# Atomizer.net
KiCad netlist of a schematic drawn in Altium Designer
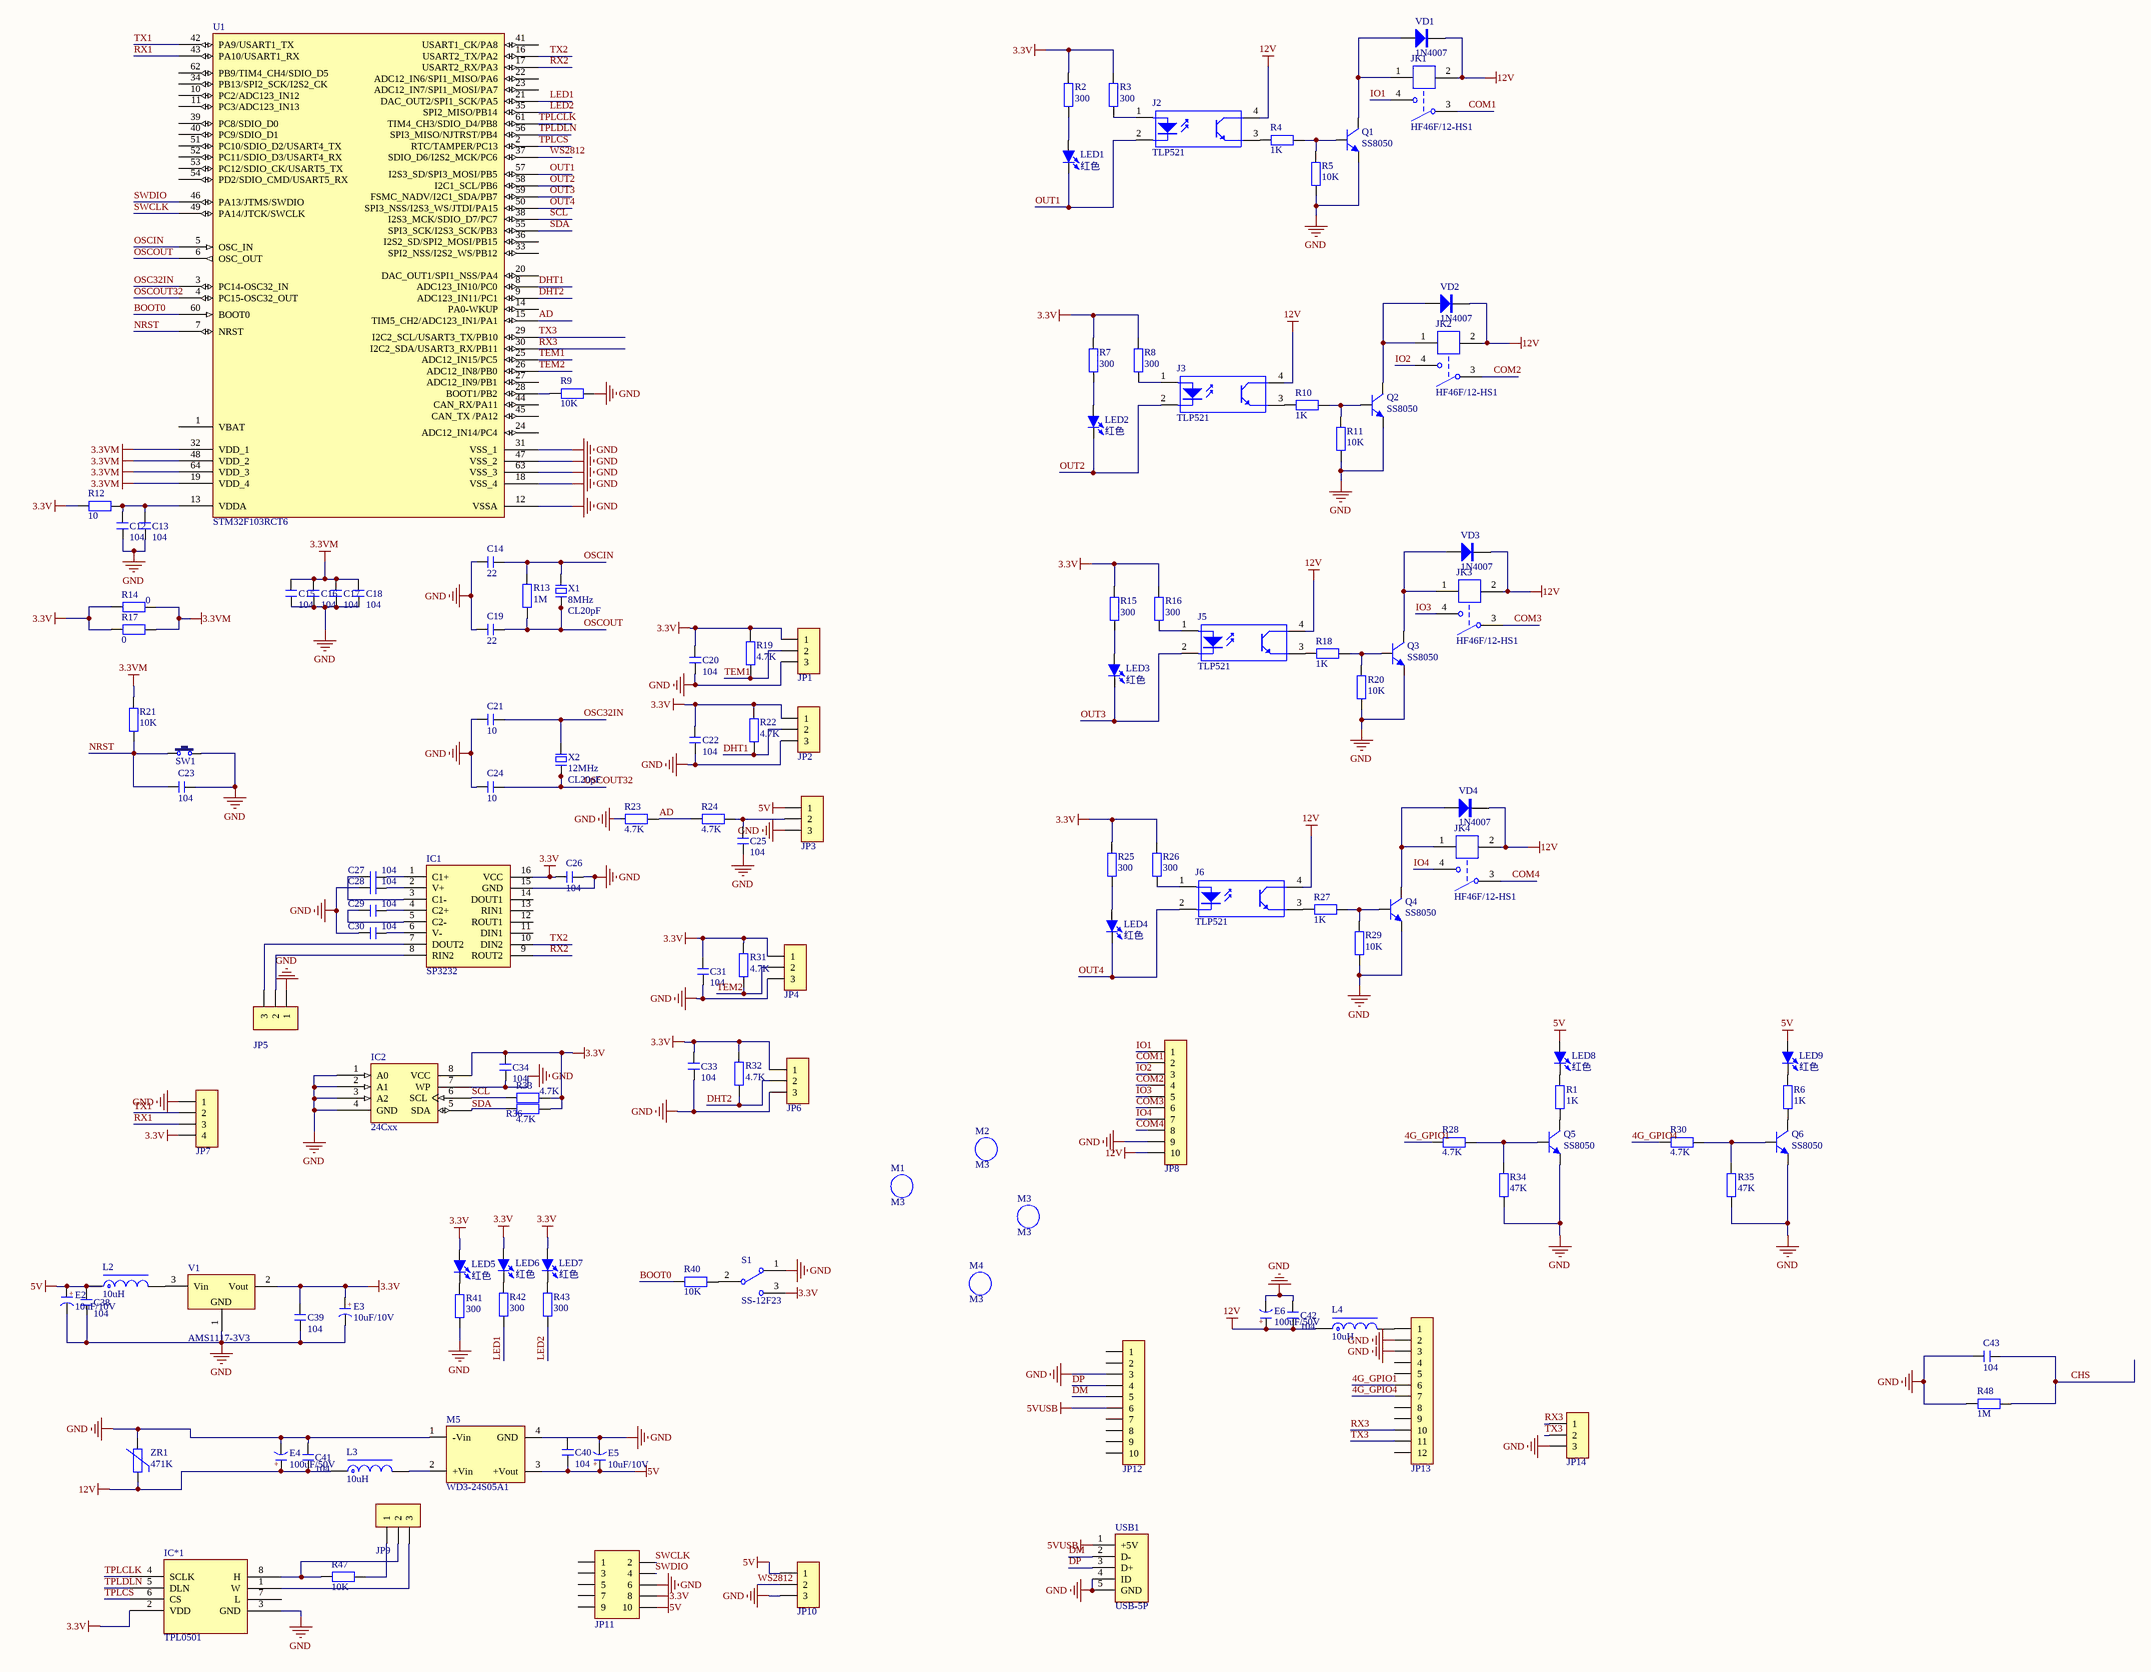
[diagram p0: Atomizer.SchDoc]

(export (version "E")
  (design (tool "Eeschema 10.0.6"))
  (components
    (comp (ref "C12")
      (value "104")
      (footprint "C 0805_M")
      (description "无极性贴片电容")
      (fields (field (name "版权归属") "源创客"))
      (libsource (lib "电阻-电容-电感") (part "C"))
    )
    (comp (ref "C13")
      (value "104")
      (footprint "C 0805_M")
      (description "无极性贴片电容")
      (fields (field (name "版权归属") "源创客"))
      (libsource (lib "电阻-电容-电感") (part "C"))
    )
    (comp (ref "C14")
      (value "22")
      (footprint "C 0805_M")
      (description "无极性贴片电容")
      (fields (field (name "版权归属") "源创客"))
      (libsource (lib "电阻-电容-电感") (part "C"))
    )
    (comp (ref "C15")
      (value "104")
      (footprint "C 0805_M")
      (description "无极性贴片电容")
      (fields (field (name "版权归属") "源创客"))
      (libsource (lib "电阻-电容-电感") (part "C"))
    )
    (comp (ref "C16")
      (value "104")
      (footprint "C 0805_M")
      (description "无极性贴片电容")
      (fields (field (name "版权归属") "源创客"))
      (libsource (lib "电阻-电容-电感") (part "C"))
    )
    (comp (ref "C17")
      (value "104")
      (footprint "C 0805_M")
      (description "无极性贴片电容")
      (fields (field (name "版权归属") "源创客"))
      (libsource (lib "电阻-电容-电感") (part "C"))
    )
    (comp (ref "C18")
      (value "104")
      (footprint "C 0805_M")
      (description "无极性贴片电容")
      (fields (field (name "版权归属") "源创客"))
      (libsource (lib "电阻-电容-电感") (part "C"))
    )
    (comp (ref "C19")
      (value "22")
      (footprint "C 0805_M")
      (description "无极性贴片电容")
      (fields (field (name "版权归属") "源创客"))
      (libsource (lib "电阻-电容-电感") (part "C"))
    )
    (comp (ref "C20")
      (value "104")
      (footprint "C 0805_M")
      (description "无极性贴片电容")
      (fields (field (name "版权归属") "源创客"))
      (libsource (lib "电阻-电容-电感") (part "C"))
    )
    (comp (ref "C21")
      (value "10")
      (footprint "C 0805_M")
      (description "无极性贴片电容")
      (fields (field (name "版权归属") "源创客"))
      (libsource (lib "电阻-电容-电感") (part "C"))
    )
    (comp (ref "C22")
      (value "104")
      (footprint "C 0805_M")
      (description "无极性贴片电容")
      (fields (field (name "版权归属") "源创客"))
      (libsource (lib "电阻-电容-电感") (part "C"))
    )
    (comp (ref "C23")
      (value "104")
      (footprint "C 0805_M")
      (description "无极性贴片电容")
      (fields (field (name "版权归属") "源创客"))
      (libsource (lib "电阻-电容-电感") (part "C"))
    )
    (comp (ref "C24")
      (value "10")
      (footprint "C 0805_M")
      (description "无极性贴片电容")
      (fields (field (name "版权归属") "源创客"))
      (libsource (lib "电阻-电容-电感") (part "C"))
    )
    (comp (ref "C25")
      (value "104")
      (footprint "C 0805_M")
      (description "无极性贴片电容")
      (fields (field (name "版权归属") "源创客"))
      (libsource (lib "电阻-电容-电感") (part "C"))
    )
    (comp (ref "C26")
      (value "104")
      (footprint "C 0805_M")
      (description "无极性贴片电容")
      (fields (field (name "版权归属") "源创客"))
      (libsource (lib "电阻-电容-电感") (part "C"))
    )
    (comp (ref "C27")
      (value "104")
      (footprint "C 0805_M")
      (description "无极性贴片电容")
      (fields (field (name "版权归属") "源创客"))
      (libsource (lib "电阻-电容-电感") (part "C"))
    )
    (comp (ref "C28")
      (value "104")
      (footprint "C 0805_M")
      (description "无极性贴片电容")
      (fields (field (name "版权归属") "源创客"))
      (libsource (lib "电阻-电容-电感") (part "C"))
    )
    (comp (ref "C29")
      (value "104")
      (footprint "C 0805_M")
      (description "无极性贴片电容")
      (fields (field (name "版权归属") "源创客"))
      (libsource (lib "电阻-电容-电感") (part "C"))
    )
    (comp (ref "C30")
      (value "104")
      (footprint "C 0805_M")
      (description "无极性贴片电容")
      (fields (field (name "版权归属") "源创客"))
      (libsource (lib "电阻-电容-电感") (part "C"))
    )
    (comp (ref "C31")
      (value "104")
      (footprint "C 0805_M")
      (description "无极性贴片电容")
      (fields (field (name "版权归属") "源创客"))
      (libsource (lib "电阻-电容-电感") (part "C"))
    )
    (comp (ref "C33")
      (value "104")
      (footprint "C 0805_M")
      (description "无极性贴片电容")
      (fields (field (name "版权归属") "源创客"))
      (libsource (lib "电阻-电容-电感") (part "C"))
    )
    (comp (ref "C34")
      (value "104")
      (footprint "C 0805_M")
      (description "无极性贴片电容")
      (fields (field (name "版权归属") "源创客"))
      (libsource (lib "电阻-电容-电感") (part "C"))
    )
    (comp (ref "C38")
      (value "104")
      (footprint "C 0805_M")
      (description "无极性贴片电容")
      (fields (field (name "版权归属") "源创客"))
      (libsource (lib "电阻-电容-电感") (part "C"))
    )
    (comp (ref "C39")
      (value "104")
      (footprint "C 0805_M")
      (description "无极性贴片电容")
      (fields (field (name "版权归属") "源创客"))
      (libsource (lib "电阻-电容-电感") (part "C"))
    )
    (comp (ref "C40")
      (value "104")
      (footprint "C 0805_M")
      (description "无极性贴片电容")
      (fields (field (name "版权归属") "源创客"))
      (libsource (lib "电阻-电容-电感") (part "C"))
    )
    (comp (ref "C41")
      (value "104")
      (footprint "C 0805_M")
      (description "无极性贴片电容")
      (fields (field (name "版权归属") "源创客"))
      (libsource (lib "电阻-电容-电感") (part "C"))
    )
    (comp (ref "C42")
      (value "104")
      (footprint "C 0805_M")
      (description "无极性贴片电容")
      (fields (field (name "版权归属") "源创客"))
      (libsource (lib "电阻-电容-电感") (part "C"))
    )
    (comp (ref "C43")
      (value "104")
      (footprint "C 1206_L")
      (description "无极性贴片电容")
      (fields (field (name "版权归属") "源创客"))
      (libsource (lib "3.1   - 电阻-电容-电感") (part "C"))
    )
    (comp (ref "E2")
      (value "10uF/10V")
      (footprint "CT 5*6 - C")
      (description "贴片固态电容")
      (fields (field (name "版权归属") "源创客"))
      (libsource (lib "3.1   - 电阻-电容-电感") (part "C-CT"))
    )
    (comp (ref "E3")
      (value "10uF/10V")
      (footprint "CM C(5*5.4)")
      (description "贴片电解电容")
      (fields (field (name "版权归属") "源创客"))
      (libsource (lib "电阻-电容-电感") (part "C-CM"))
    )
    (comp (ref "E4")
      (value "100uF/50V")
      (footprint "CT 10*8 - C")
      (description "贴片固态电容")
      (fields (field (name "版权归属") "源创客"))
      (libsource (lib "3.1   - 电阻-电容-电感") (part "C-CT"))
    )
    (comp (ref "E5")
      (value "10uF/10V")
      (footprint "CT 5*6 - C")
      (description "贴片固态电容")
      (fields (field (name "版权归属") "源创客"))
      (libsource (lib "3.1   - 电阻-电容-电感") (part "C-CT"))
    )
    (comp (ref "E6")
      (value "100uF/50V")
      (footprint "CT 10*8 - C")
      (description "贴片固态电容")
      (fields (field (name "版权归属") "源创客"))
      (libsource (lib "3.1   - 电阻-电容-电感") (part "C-CT"))
    )
    (comp (ref "IC*1")
      (value "TPL0501")
      (footprint "SOT23-8L")
      (description "数字电位器")
      (libsource (lib "IC芯片") (part "TPL0501"))
    )
    (comp (ref "IC1")
      (value "SP3232")
      (footprint "TSSOP-16")
      (description "RS232通讯芯片")
      (fields (field (name "版权归属") "源创客"))
      (libsource (lib "IC芯片") (part "SP3232"))
    )
    (comp (ref "IC2")
      (value "24Cxx")
      (footprint "SOP8_L")
      (description "外置EEPROM")
      (fields (field (name "版权归属") "源创客"))
      (libsource (lib "IC芯片") (part "24Cxx"))
    )
    (comp (ref "J2")
      (value "TLP521")
      (footprint "DIP4-300")
      (description "开关光耦")
      (fields (field (name "版权归属") "源创客"))
      (libsource (lib "传感元件") (part "TLP521"))
    )
    (comp (ref "J3")
      (value "TLP521")
      (footprint "DIP4-300")
      (description "开关光耦")
      (fields (field (name "版权归属") "源创客"))
      (libsource (lib "传感元件") (part "TLP521"))
    )
    (comp (ref "J5")
      (value "TLP521")
      (footprint "DIP4-300")
      (description "开关光耦")
      (fields (field (name "版权归属") "源创客"))
      (libsource (lib "传感元件") (part "TLP521"))
    )
    (comp (ref "J6")
      (value "TLP521")
      (footprint "DIP4-300")
      (description "开关光耦")
      (fields (field (name "版权归属") "源创客"))
      (libsource (lib "传感元件") (part "TLP521"))
    )
    (comp (ref "JK1")
      (value "HF46F/12-HS1")
      (footprint "HF46-xx-HS1")
      (description "12V一组常开")
      (fields (field (name "版权归属") "源创客"))
      (libsource (lib "7.1   - 继电器") (part "HF46F/12-HS1"))
    )
    (comp (ref "JK2")
      (value "HF46F/12-HS1")
      (footprint "HF46-xx-HS1")
      (description "12V一组常开")
      (fields (field (name "版权归属") "源创客"))
      (libsource (lib "7.1   - 继电器") (part "HF46F/12-HS1"))
    )
    (comp (ref "JK3")
      (value "HF46F/12-HS1")
      (footprint "HF46-xx-HS1")
      (description "12V一组常开")
      (fields (field (name "版权归属") "源创客"))
      (libsource (lib "7.1   - 继电器") (part "HF46F/12-HS1"))
    )
    (comp (ref "JK4")
      (value "HF46F/12-HS1")
      (footprint "HF46-xx-HS1")
      (description "12V一组常开")
      (fields (field (name "版权归属") "源创客"))
      (libsource (lib "7.1   - 继电器") (part "HF46F/12-HS1"))
    )
    (comp (ref "JP1")
      (value "HDR-1X3")
      (footprint "KF128-3.81-3P")
      (description "3P接插件")
      (fields (field (name "版权归属") "源创客"))
      (libsource (lib "接插件") (part "Header 3"))
    )
    (comp (ref "JP2")
      (value "HDR-1X3")
      (footprint "KF128-3.81-3P")
      (description "3P接插件")
      (fields (field (name "版权归属") "源创客"))
      (libsource (lib "接插件") (part "Header 3"))
    )
    (comp (ref "JP3")
      (value "HDR-1X3")
      (footprint "KF128-3.81-3P")
      (description "3P接插件")
      (fields (field (name "版权归属") "源创客"))
      (libsource (lib "接插件") (part "Header 3"))
    )
    (comp (ref "JP4")
      (value "HDR-1X3")
      (footprint "KF128-3.81-3P")
      (description "3P接插件")
      (fields (field (name "版权归属") "源创客"))
      (libsource (lib "接插件") (part "Header 3"))
    )
    (comp (ref "JP5")
      (value "HDR-1X3")
      (footprint "XH2.54-LI-3P")
      (description "3P接插件")
      (fields (field (name "版权归属") "源创客"))
      (libsource (lib "4.6   - 接插件-脚距2.54") (part "Header 3"))
    )
    (comp (ref "JP6")
      (value "HDR-1X3")
      (footprint "KF128-3.81-3P")
      (description "3P接插件")
      (fields (field (name "版权归属") "源创客"))
      (libsource (lib "接插件") (part "Header 3"))
    )
    (comp (ref "JP7")
      (value "HDR-1X4")
      (footprint "HDR2.54-LI-4P")
      (description "4P接插件")
      (fields (field (name "版权归属") "源创客"))
      (libsource (lib "4.6   - 接插件-脚距2.54") (part "Header 4"))
    )
    (comp (ref "JP8")
      (value "HDR-1X10")
      (footprint "KF128-5.08-10P")
      (description "10P接插件")
      (fields (field (name "版权归属") "源创客"))
      (libsource (lib "接插件") (part "Header 10"))
    )
    (comp (ref "JP9")
      (value "HDR-1X3")
      (footprint "KF128-3.81-3P")
      (description "3P接插件")
      (fields (field (name "版权归属") "源创客"))
      (libsource (lib "") (part "Header 3_1"))
    )
    (comp (ref "JP10")
      (value "HDR-1X3")
      (footprint "KF128-3.81-3P")
      (description "3P接插件")
      (fields (field (name "版权归属") "源创客"))
      (libsource (lib "接插件") (part "Header 3"))
    )
    (comp (ref "JP11")
      (value "Header 5X2")
      (footprint "IDC2.54-LI-2x5P")
      (description "5*2P接插件")
      (fields (field (name "版权归属") "源创客"))
      (libsource (lib "4.6   - 接插件-脚距2.54") (part "Header 5X2"))
    )
    (comp (ref "JP12")
      (value "HDR-1X10")
      (footprint "HDR2.54-M-LI-10P")
      (description "10P接插件")
      (fields (field (name "版权归属") "源创客"))
      (libsource (lib "4.6   - 接插件-脚距2.54") (part "Header 10"))
    )
    (comp (ref "JP13")
      (value "HDR-1X12")
      (footprint "HDR2.54-M-LI-12P")
      (description "12P接插件")
      (fields (field (name "版权归属") "源创客"))
      (libsource (lib "4.6   - 接插件-脚距2.54") (part "Header 12"))
    )
    (comp (ref "JP14")
      (value "HDR-1X3")
      (footprint "HDR2.54-LI-3P")
      (description "3P接插件")
      (fields (field (name "版权归属") "源创客"))
      (libsource (lib "") (part "Header 3_1"))
    )
    (comp (ref "L2")
      (value "10uH")
      (footprint "CD32")
      (description "贴片功率电感")
      (fields (field (name "版权归属") "源创客"))
      (libsource (lib "3.1   - 电阻-电容-电感") (part "L-CD"))
    )
    (comp (ref "L3")
      (value "10uH")
      (footprint "CD32")
      (description "贴片功率电感")
      (fields (field (name "版权归属") "源创客"))
      (libsource (lib "3.1   - 电阻-电容-电感") (part "L-CD"))
    )
    (comp (ref "L4")
      (value "10uH")
      (footprint "CD32")
      (description "贴片功率电感")
      (fields (field (name "版权归属") "源创客"))
      (libsource (lib "3.1   - 电阻-电容-电感") (part "L-CD"))
    )
    (comp (ref "LED1")
      (value "红色")
      (footprint "0805_LED_S1")
      (description "贴片LED")
      (fields (field (name "版权归属") "源创客"))
      (libsource (lib "LED") (part "LED-SMD"))
    )
    (comp (ref "LED2")
      (value "红色")
      (footprint "0805_LED_S1")
      (description "贴片LED")
      (fields (field (name "版权归属") "源创客"))
      (libsource (lib "LED") (part "LED-SMD"))
    )
    (comp (ref "LED3")
      (value "红色")
      (footprint "0805_LED_S1")
      (description "贴片LED")
      (fields (field (name "版权归属") "源创客"))
      (libsource (lib "LED") (part "LED-SMD"))
    )
    (comp (ref "LED4")
      (value "红色")
      (footprint "0805_LED_S1")
      (description "贴片LED")
      (fields (field (name "版权归属") "源创客"))
      (libsource (lib "LED") (part "LED-SMD"))
    )
    (comp (ref "LED5")
      (value "红色")
      (footprint "0805_LED_S1")
      (description "贴片LED")
      (fields (field (name "版权归属") "源创客"))
      (libsource (lib "LED") (part "LED-SMD"))
    )
    (comp (ref "LED6")
      (value "红色")
      (footprint "0805_LED_S1")
      (description "贴片LED")
      (fields (field (name "版权归属") "源创客"))
      (libsource (lib "LED") (part "LED-SMD"))
    )
    (comp (ref "LED7")
      (value "红色")
      (footprint "0805_LED_S1")
      (description "贴片LED")
      (fields (field (name "版权归属") "源创客"))
      (libsource (lib "LED") (part "LED-SMD"))
    )
    (comp (ref "LED8")
      (value "红色")
      (footprint "0805_LED_S1")
      (description "贴片LED")
      (fields (field (name "版权归属") "源创客"))
      (libsource (lib "LED") (part "LED-SMD"))
    )
    (comp (ref "LED9")
      (value "红色")
      (footprint "0805_LED_S1")
      (description "贴片LED")
      (fields (field (name "版权归属") "源创客"))
      (libsource (lib "LED") (part "LED-SMD"))
    )
    (comp (ref "M1")
      (value "M3")
      (footprint "M3 125X200")
      (description "铜柱孔")
      (fields (field (name "版权归属") "源创客"))
      (libsource (lib "未分类器件") (part "M3"))
    )
    (comp (ref "M2")
      (value "M3")
      (footprint "M3 125X200")
      (description "铜柱孔")
      (fields (field (name "版权归属") "源创客"))
      (libsource (lib "未分类器件") (part "M3"))
    )
    (comp (ref "M3")
      (value "M3")
      (footprint "M3 125X200")
      (description "铜柱孔")
      (fields (field (name "版权归属") "源创客"))
      (libsource (lib "未分类器件") (part "M3"))
    )
    (comp (ref "M4")
      (value "M3")
      (footprint "M3 125X200")
      (description "铜柱孔")
      (fields (field (name "版权归属") "源创客"))
      (libsource (lib "未分类器件") (part "M3"))
    )
    (comp (ref "M5")
      (value "WD3-24S05A1")
      (footprint "WD-24S05A1")
      (description "24V转5V模块")
      (fields (field (name "版权归属") "源创客"))
      (libsource (lib "13.1 - 模块") (part "WD3-24S05A1"))
    )
    (comp (ref "Q1")
      (value "SS8050")
      (footprint "SOT23-3N")
      (description "高频放大-NPN型")
      (fields (field (name "版权归属") "源创客"))
      (libsource (lib "三极管") (part "8050-SMD"))
    )
    (comp (ref "Q2")
      (value "SS8050")
      (footprint "SOT23-3N")
      (description "高频放大-NPN型")
      (fields (field (name "版权归属") "源创客"))
      (libsource (lib "三极管") (part "8050-SMD"))
    )
    (comp (ref "Q3")
      (value "SS8050")
      (footprint "SOT23-3N")
      (description "高频放大-NPN型")
      (fields (field (name "版权归属") "源创客"))
      (libsource (lib "三极管") (part "8050-SMD"))
    )
    (comp (ref "Q4")
      (value "SS8050")
      (footprint "SOT23-3N")
      (description "高频放大-NPN型")
      (fields (field (name "版权归属") "源创客"))
      (libsource (lib "三极管") (part "8050-SMD"))
    )
    (comp (ref "Q5")
      (value "SS8050")
      (footprint "SOT23-3N")
      (description "高频放大-NPN型")
      (fields (field (name "版权归属") "源创客"))
      (libsource (lib "6.2   - 三极管") (part "8050-SMD"))
    )
    (comp (ref "Q6")
      (value "SS8050")
      (footprint "SOT23-3N")
      (description "高频放大-NPN型")
      (fields (field (name "版权归属") "源创客"))
      (libsource (lib "6.2   - 三极管") (part "8050-SMD"))
    )
    (comp (ref "R1")
      (value "1K")
      (footprint "R 0805_M")
      (description "贴片电阻")
      (fields (field (name "版权归属") "源创客"))
      (libsource (lib "电阻-电容-电感") (part "R"))
    )
    (comp (ref "R2")
      (value "300")
      (footprint "R 0805_M")
      (description "贴片电阻")
      (fields (field (name "版权归属") "源创客"))
      (libsource (lib "电阻-电容-电感") (part "R"))
    )
    (comp (ref "R3")
      (value "300")
      (footprint "R 0805_M")
      (description "贴片电阻")
      (fields (field (name "版权归属") "源创客"))
      (libsource (lib "电阻-电容-电感") (part "R"))
    )
    (comp (ref "R4")
      (value "1K")
      (footprint "R 0805_M")
      (description "贴片电阻")
      (fields (field (name "版权归属") "源创客"))
      (libsource (lib "电阻-电容-电感") (part "R"))
    )
    (comp (ref "R5")
      (value "10K")
      (footprint "R 0805_M")
      (description "贴片电阻")
      (fields (field (name "版权归属") "源创客"))
      (libsource (lib "电阻-电容-电感") (part "R"))
    )
    (comp (ref "R6")
      (value "1K")
      (footprint "R 0805_M")
      (description "贴片电阻")
      (fields (field (name "版权归属") "源创客"))
      (libsource (lib "电阻-电容-电感") (part "R"))
    )
    (comp (ref "R7")
      (value "300")
      (footprint "R 0805_M")
      (description "贴片电阻")
      (fields (field (name "版权归属") "源创客"))
      (libsource (lib "电阻-电容-电感") (part "R"))
    )
    (comp (ref "R8")
      (value "300")
      (footprint "R 0805_M")
      (description "贴片电阻")
      (fields (field (name "版权归属") "源创客"))
      (libsource (lib "电阻-电容-电感") (part "R"))
    )
    (comp (ref "R9")
      (value "10K")
      (footprint "R 0805_M")
      (description "贴片电阻")
      (fields (field (name "版权归属") "源创客"))
      (libsource (lib "电阻-电容-电感") (part "R"))
    )
    (comp (ref "R10")
      (value "1K")
      (footprint "R 0805_M")
      (description "贴片电阻")
      (fields (field (name "版权归属") "源创客"))
      (libsource (lib "电阻-电容-电感") (part "R"))
    )
    (comp (ref "R11")
      (value "10K")
      (footprint "R 0805_M")
      (description "贴片电阻")
      (fields (field (name "版权归属") "源创客"))
      (libsource (lib "电阻-电容-电感") (part "R"))
    )
    (comp (ref "R12")
      (value "10")
      (footprint "R 0805_M")
      (description "贴片电阻")
      (fields (field (name "版权归属") "源创客"))
      (libsource (lib "电阻-电容-电感") (part "R"))
    )
    (comp (ref "R13")
      (value "1M")
      (footprint "R 0805_M")
      (description "贴片电阻")
      (fields (field (name "版权归属") "源创客"))
      (libsource (lib "电阻-电容-电感") (part "R"))
    )
    (comp (ref "R14")
      (value "0")
      (footprint "R 0805_M")
      (description "贴片电阻")
      (fields (field (name "版权归属") "源创客"))
      (libsource (lib "电阻-电容-电感") (part "R"))
    )
    (comp (ref "R15")
      (value "300")
      (footprint "R 0805_M")
      (description "贴片电阻")
      (fields (field (name "版权归属") "源创客"))
      (libsource (lib "电阻-电容-电感") (part "R"))
    )
    (comp (ref "R16")
      (value "300")
      (footprint "R 0805_M")
      (description "贴片电阻")
      (fields (field (name "版权归属") "源创客"))
      (libsource (lib "电阻-电容-电感") (part "R"))
    )
    (comp (ref "R17")
      (value "0")
      (footprint "R 0805_M")
      (description "贴片电阻")
      (fields (field (name "版权归属") "源创客"))
      (libsource (lib "电阻-电容-电感") (part "R"))
    )
    (comp (ref "R18")
      (value "1K")
      (footprint "R 0805_M")
      (description "贴片电阻")
      (fields (field (name "版权归属") "源创客"))
      (libsource (lib "电阻-电容-电感") (part "R"))
    )
    (comp (ref "R19")
      (value "4.7K")
      (footprint "R 0805_M")
      (description "贴片电阻")
      (fields (field (name "版权归属") "源创客"))
      (libsource (lib "电阻-电容-电感") (part "R"))
    )
    (comp (ref "R20")
      (value "10K")
      (footprint "R 0805_M")
      (description "贴片电阻")
      (fields (field (name "版权归属") "源创客"))
      (libsource (lib "电阻-电容-电感") (part "R"))
    )
    (comp (ref "R21")
      (value "10K")
      (footprint "R 0805_M")
      (description "贴片电阻")
      (fields (field (name "版权归属") "源创客"))
      (libsource (lib "电阻-电容-电感") (part "R"))
    )
    (comp (ref "R22")
      (value "4.7K")
      (footprint "R 0805_M")
      (description "贴片电阻")
      (fields (field (name "版权归属") "源创客"))
      (libsource (lib "电阻-电容-电感") (part "R"))
    )
    (comp (ref "R23")
      (value "4.7K")
      (footprint "R 0805_M")
      (description "贴片电阻")
      (fields (field (name "版权归属") "源创客"))
      (libsource (lib "电阻-电容-电感") (part "R"))
    )
    (comp (ref "R24")
      (value "4.7K")
      (footprint "R 0805_M")
      (description "贴片电阻")
      (fields (field (name "版权归属") "源创客"))
      (libsource (lib "电阻-电容-电感") (part "R"))
    )
    (comp (ref "R25")
      (value "300")
      (footprint "R 0805_M")
      (description "贴片电阻")
      (fields (field (name "版权归属") "源创客"))
      (libsource (lib "电阻-电容-电感") (part "R"))
    )
    (comp (ref "R26")
      (value "300")
      (footprint "R 0805_M")
      (description "贴片电阻")
      (fields (field (name "版权归属") "源创客"))
      (libsource (lib "电阻-电容-电感") (part "R"))
    )
    (comp (ref "R27")
      (value "1K")
      (footprint "R 0805_M")
      (description "贴片电阻")
      (fields (field (name "版权归属") "源创客"))
      (libsource (lib "电阻-电容-电感") (part "R"))
    )
    (comp (ref "R28")
      (value "4.7K")
      (footprint "R 0805_M")
      (description "贴片电阻")
      (fields (field (name "版权归属") "源创客"))
      (libsource (lib "电阻-电容-电感") (part "R"))
    )
    (comp (ref "R29")
      (value "10K")
      (footprint "R 0805_M")
      (description "贴片电阻")
      (fields (field (name "版权归属") "源创客"))
      (libsource (lib "电阻-电容-电感") (part "R"))
    )
    (comp (ref "R30")
      (value "4.7K")
      (footprint "R 0805_M")
      (description "贴片电阻")
      (fields (field (name "版权归属") "源创客"))
      (libsource (lib "电阻-电容-电感") (part "R"))
    )
    (comp (ref "R31")
      (value "4.7K")
      (footprint "R 0805_M")
      (description "贴片电阻")
      (fields (field (name "版权归属") "源创客"))
      (libsource (lib "电阻-电容-电感") (part "R"))
    )
    (comp (ref "R32")
      (value "4.7K")
      (footprint "R 0805_M")
      (description "贴片电阻")
      (fields (field (name "版权归属") "源创客"))
      (libsource (lib "电阻-电容-电感") (part "R"))
    )
    (comp (ref "R33")
      (value "4.7K")
      (footprint "R 0805_M")
      (description "贴片电阻")
      (fields (field (name "版权归属") "源创客"))
      (libsource (lib "电阻-电容-电感") (part "R"))
    )
    (comp (ref "R34")
      (value "47K")
      (footprint "R 0805_M")
      (description "贴片电阻")
      (fields (field (name "版权归属") "源创客"))
      (libsource (lib "电阻-电容-电感") (part "R"))
    )
    (comp (ref "R35")
      (value "47K")
      (footprint "R 0805_M")
      (description "贴片电阻")
      (fields (field (name "版权归属") "源创客"))
      (libsource (lib "电阻-电容-电感") (part "R"))
    )
    (comp (ref "R36")
      (value "4.7K")
      (footprint "R 0805_M")
      (description "贴片电阻")
      (fields (field (name "版权归属") "源创客"))
      (libsource (lib "电阻-电容-电感") (part "R"))
    )
    (comp (ref "R40")
      (value "10K")
      (footprint "R 0805_M")
      (description "贴片电阻")
      (fields (field (name "版权归属") "源创客"))
      (libsource (lib "电阻-电容-电感") (part "R"))
    )
    (comp (ref "R41")
      (value "300")
      (footprint "R 0805_M")
      (description "贴片电阻")
      (fields (field (name "版权归属") "源创客"))
      (libsource (lib "电阻-电容-电感") (part "R"))
    )
    (comp (ref "R42")
      (value "300")
      (footprint "R 0805_M")
      (description "贴片电阻")
      (fields (field (name "版权归属") "源创客"))
      (libsource (lib "电阻-电容-电感") (part "R"))
    )
    (comp (ref "R43")
      (value "300")
      (footprint "R 0805_M")
      (description "贴片电阻")
      (fields (field (name "版权归属") "源创客"))
      (libsource (lib "电阻-电容-电感") (part "R"))
    )
    (comp (ref "R47")
      (value "10K")
      (footprint "R 0805_M")
      (description "贴片电阻")
      (fields (field (name "版权归属") "源创客"))
      (libsource (lib "电阻-电容-电感") (part "R"))
    )
    (comp (ref "R48")
      (value "1M")
      (footprint "R 1206_L")
      (description "贴片电阻")
      (fields (field (name "版权归属") "源创客"))
      (libsource (lib "3.1   - 电阻-电容-电感") (part "R"))
    )
    (comp (ref "S1")
      (value "SS-12F23")
      (footprint "MSK-12C01-07")
      (description "1路波动开关")
      (fields (field (name "版权归属") "源创客"))
      (libsource (lib "按键-开关") (part "SSW-1P"))
    )
    (comp (ref "SW1")
      (value "3x6x5")
      (footprint "TSW SMD-3*6*2.5")
      (description "3x6轻触开关")
      (fields (field (name "版权归属") "源创客"))
      (libsource (lib "按键-开关") (part "TSW 3x6"))
    )
    (comp (ref "U1")
      (value "STM32F103RCT6")
      (footprint "LQFP64 10X10_N")
      (description "32位STM单片机")
      (fields (field (name "版权归属") "源创客"))
      (libsource (lib "STM32系列单片机") (part "STM32F103RE"))
    )
    (comp (ref "USB1")
      (value "USB-5P")
      (footprint "USB-MICRO_A")
      (description "微型USB母座")
      (fields (field (name "版权归属") "源创客"))
      (libsource (lib "4.1   - 接口类") (part "USB-5P"))
    )
    (comp (ref "V1")
      (value "AMS1117-3V3")
      (footprint "SOT223_L")
      (description "三端稳压芯片")
      (fields (field (name "版权归属") "源创客"))
      (libsource (lib "IC芯片") (part "AMS1117"))
    )
    (comp (ref "VD1")
      (value "1N4007")
      (footprint "SMA(DO-214AC)_S1")
      (description "整流二极管")
      (fields (field (name "版权归属") "源创客"))
      (libsource (lib "二极管-整流桥") (part "1N4007"))
    )
    (comp (ref "VD2")
      (value "1N4007")
      (footprint "SMA(DO-214AC)_S1")
      (description "整流二极管")
      (fields (field (name "版权归属") "源创客"))
      (libsource (lib "二极管-整流桥") (part "1N4007"))
    )
    (comp (ref "VD3")
      (value "1N4007")
      (footprint "SMA(DO-214AC)_S1")
      (description "整流二极管")
      (fields (field (name "版权归属") "源创客"))
      (libsource (lib "二极管-整流桥") (part "1N4007"))
    )
    (comp (ref "VD4")
      (value "1N4007")
      (footprint "SMA(DO-214AC)_S1")
      (description "整流二极管")
      (fields (field (name "版权归属") "源创客"))
      (libsource (lib "二极管-整流桥") (part "1N4007"))
    )
    (comp (ref "X1")
      (value "8MHz")
      (footprint "SMD-5032_2P")
      (description "2脚无源脚晶振")
      (fields (field (name "负载电容") "CL20pF") (field (name "版权归属") "源创客"))
      (libsource (lib "10.1 - 保险丝-晶振") (part "XTAL-2P"))
    )
    (comp (ref "X2")
      (value "12MHz")
      (footprint "OSC-3x10-LI")
      (description "2脚无源脚晶振")
      (fields (field (name "负载电容") "CL20pF") (field (name "版权归属") "源创客"))
      (libsource (lib "10.1 - 保险丝-晶振") (part "XTAL-2P"))
    )
    (comp (ref "ZR1")
      (value "471K")
      (footprint "VDR 9D-4.5")
      (description "压敏电阻")
      (fields (field (name "版权归属") "源创客"))
      (libsource (lib "3.1   - 电阻-电容-电感") (part "R_VDR"))
    )
  )
  (nets
    (net (code "1") (name "/4G_GPIO1") (class "Default")
      (node (ref "JP13") (pin "6") (pinfunction "6_6") (pintype "passive"))
      (node (ref "R28") (pin "2") (pinfunction "2_2") (pintype "passive"))
    )
    (net (code "2") (name "/4G_GPIO4") (class "Default")
      (node (ref "JP13") (pin "7") (pinfunction "7_7") (pintype "passive"))
      (node (ref "R30") (pin "2") (pinfunction "2_2") (pintype "passive"))
    )
    (net (code "3") (name "/AD") (class "Default")
      (node (ref "R23") (pin "2") (pinfunction "2_2") (pintype "passive"))
      (node (ref "R24") (pin "1") (pinfunction "1_1") (pintype "passive"))
      (node (ref "U1") (pin "15") (pinfunction "TIM5_CH2/ADC123_IN1/PA1_15") (pintype "bidirectional"))
    )
    (net (code "4") (name "/BOOT0") (class "Default")
      (node (ref "R40") (pin "1") (pinfunction "1_1") (pintype "passive"))
      (node (ref "U1") (pin "60") (pinfunction "BOOT0_60") (pintype "input"))
    )
    (net (code "5") (name "/CHS") (class "Default")
      (node (ref "C43") (pin "2") (pinfunction "2_2") (pintype "passive"))
      (node (ref "R48") (pin "2") (pinfunction "2_2") (pintype "passive"))
    )
    (net (code "6") (name "/COM1") (class "Default")
      (node (ref "JK1") (pin "3") (pinfunction "3_3") (pintype "passive"))
      (node (ref "JP8") (pin "2") (pinfunction "2_2") (pintype "passive"))
    )
    (net (code "7") (name "/COM2") (class "Default")
      (node (ref "JK2") (pin "3") (pinfunction "3_3") (pintype "passive"))
      (node (ref "JP8") (pin "4") (pinfunction "4_4") (pintype "passive"))
    )
    (net (code "8") (name "/COM3") (class "Default")
      (node (ref "JK3") (pin "3") (pinfunction "3_3") (pintype "passive"))
      (node (ref "JP8") (pin "6") (pinfunction "6_6") (pintype "passive"))
    )
    (net (code "9") (name "/COM4") (class "Default")
      (node (ref "JK4") (pin "3") (pinfunction "3_3") (pintype "passive"))
      (node (ref "JP8") (pin "8") (pinfunction "8_8") (pintype "passive"))
    )
    (net (code "10") (name "/DHT1") (class "Default")
      (node (ref "JP2") (pin "2") (pinfunction "2_2") (pintype "passive"))
      (node (ref "R22") (pin "1") (pinfunction "1_1") (pintype "passive"))
      (node (ref "U1") (pin "8") (pinfunction "ADC123_IN10/PC0_8") (pintype "bidirectional"))
    )
    (net (code "11") (name "/DHT2") (class "Default")
      (node (ref "JP6") (pin "2") (pinfunction "2_2") (pintype "passive"))
      (node (ref "R32") (pin "1") (pinfunction "1_1") (pintype "passive"))
      (node (ref "U1") (pin "9") (pinfunction "ADC123_IN11/PC1_9") (pintype "bidirectional"))
    )
    (net (code "12") (name "/DM") (class "Default")
      (node (ref "JP12") (pin "5") (pinfunction "5_5") (pintype "passive"))
      (node (ref "USB1") (pin "2") (pinfunction "D-_2") (pintype "passive"))
    )
    (net (code "13") (name "/DP") (class "Default")
      (node (ref "JP12") (pin "4") (pinfunction "4_4") (pintype "passive"))
      (node (ref "USB1") (pin "3") (pinfunction "D+_3") (pintype "passive"))
    )
    (net (code "14") (name "/IO1") (class "Default")
      (node (ref "JK1") (pin "4") (pinfunction "4_4") (pintype "passive"))
      (node (ref "JP8") (pin "1") (pinfunction "1_1") (pintype "passive"))
    )
    (net (code "15") (name "/IO2") (class "Default")
      (node (ref "JK2") (pin "4") (pinfunction "4_4") (pintype "passive"))
      (node (ref "JP8") (pin "3") (pinfunction "3_3") (pintype "passive"))
    )
    (net (code "16") (name "/IO3") (class "Default")
      (node (ref "JK3") (pin "4") (pinfunction "4_4") (pintype "passive"))
      (node (ref "JP8") (pin "5") (pinfunction "5_5") (pintype "passive"))
    )
    (net (code "17") (name "/IO4") (class "Default")
      (node (ref "JK4") (pin "4") (pinfunction "4_4") (pintype "passive"))
      (node (ref "JP8") (pin "7") (pinfunction "7_7") (pintype "passive"))
    )
    (net (code "18") (name "/LED1") (class "Default")
      (node (ref "R42") (pin "1") (pinfunction "1_1") (pintype "passive"))
      (node (ref "U1") (pin "21") (pinfunction "DAC_OUT2/SPI1_SCK/PA5_21") (pintype "bidirectional"))
    )
    (net (code "19") (name "/LED2") (class "Default")
      (node (ref "R43") (pin "1") (pinfunction "1_1") (pintype "passive"))
      (node (ref "U1") (pin "35") (pinfunction "SPI2_MISO/PB14_35") (pintype "bidirectional"))
    )
    (net (code "20") (name "/NRST") (class "Default")
      (node (ref "C23") (pin "1") (pinfunction "1_1") (pintype "passive"))
      (node (ref "R21") (pin "1") (pinfunction "1_1") (pintype "passive"))
      (node (ref "SW1") (pin "1") (pinfunction "1_1") (pintype "passive"))
      (node (ref "U1") (pin "7") (pinfunction "NRST_7") (pintype "bidirectional"))
    )
    (net (code "21") (name "/OSC32IN") (class "Default")
      (node (ref "C21") (pin "1") (pinfunction "1_1") (pintype "passive"))
      (node (ref "U1") (pin "3") (pinfunction "PC14-OSC32_IN_3") (pintype "bidirectional"))
      (node (ref "X2") (pin "2") (pinfunction "2_2") (pintype "passive"))
    )
    (net (code "22") (name "/OSCIN") (class "Default")
      (node (ref "C14") (pin "1") (pinfunction "1_1") (pintype "passive"))
      (node (ref "R13") (pin "2") (pinfunction "2_2") (pintype "passive"))
      (node (ref "U1") (pin "5") (pinfunction "OSC_IN_5") (pintype "input"))
      (node (ref "X1") (pin "2") (pinfunction "2_2") (pintype "passive"))
    )
    (net (code "23") (name "/OSCOUT") (class "Default")
      (node (ref "C19") (pin "1") (pinfunction "1_1") (pintype "passive"))
      (node (ref "R13") (pin "1") (pinfunction "1_1") (pintype "passive"))
      (node (ref "U1") (pin "6") (pinfunction "OSC_OUT_6") (pintype "output"))
      (node (ref "X1") (pin "1") (pinfunction "1_1") (pintype "passive"))
    )
    (net (code "24") (name "/OSCOUT32") (class "Default")
      (node (ref "C24") (pin "1") (pinfunction "1_1") (pintype "passive"))
      (node (ref "U1") (pin "4") (pinfunction "PC15-OSC32_OUT_4") (pintype "bidirectional"))
      (node (ref "X2") (pin "1") (pinfunction "1_1") (pintype "passive"))
    )
    (net (code "25") (name "/OUT1") (class "Default")
      (node (ref "J2") (pin "2") (pinfunction "K_2") (pintype "passive"))
      (node (ref "LED1") (pin "2") (pinfunction "K_2") (pintype "passive"))
      (node (ref "U1") (pin "57") (pinfunction "I2S3_SD/SPI3_MOSI/PB5_57") (pintype "bidirectional"))
    )
    (net (code "26") (name "/OUT2") (class "Default")
      (node (ref "J3") (pin "2") (pinfunction "K_2") (pintype "passive"))
      (node (ref "LED2") (pin "2") (pinfunction "K_2") (pintype "passive"))
      (node (ref "U1") (pin "58") (pinfunction "I2C1_SCL/PB6_58") (pintype "bidirectional"))
    )
    (net (code "27") (name "/OUT3") (class "Default")
      (node (ref "J5") (pin "2") (pinfunction "K_2") (pintype "passive"))
      (node (ref "LED3") (pin "2") (pinfunction "K_2") (pintype "passive"))
      (node (ref "U1") (pin "59") (pinfunction "FSMC_NADV/I2C1_SDA/PB7_59") (pintype "bidirectional"))
    )
    (net (code "28") (name "/OUT4") (class "Default")
      (node (ref "J6") (pin "2") (pinfunction "K_2") (pintype "passive"))
      (node (ref "LED4") (pin "2") (pinfunction "K_2") (pintype "passive"))
      (node (ref "U1") (pin "50") (pinfunction "SPI3_NSS/I2S3_WS/JTDI/PA15_50") (pintype "bidirectional"))
    )
    (net (code "29") (name "/RX1") (class "Default")
      (node (ref "JP7") (pin "3") (pinfunction "3_3") (pintype "passive"))
      (node (ref "U1") (pin "43") (pinfunction "PA10/USART1_RX_43") (pintype "bidirectional"))
    )
    (net (code "30") (name "/RX2") (class "Default")
      (node (ref "IC1") (pin "9") (pinfunction "ROUT2_9") (pintype "passive"))
      (node (ref "U1") (pin "17") (pinfunction "USART2_RX/PA3_17") (pintype "bidirectional"))
    )
    (net (code "31") (name "/RX3") (class "Default")
      (node (ref "JP13") (pin "10") (pinfunction "10_10") (pintype "passive"))
      (node (ref "JP14") (pin "1") (pinfunction "1_1") (pintype "passive"))
      (node (ref "U1") (pin "30") (pinfunction "I2C2_SDA/USART3_RX/PB11_30") (pintype "bidirectional"))
    )
    (net (code "32") (name "/SCL") (class "Default")
      (node (ref "IC2") (pin "6") (pinfunction "SCL_6") (pintype "input"))
      (node (ref "R33") (pin "1") (pinfunction "1_1") (pintype "passive"))
      (node (ref "U1") (pin "38") (pinfunction "I2S3_MCK/SDIO_D7/PC7_38") (pintype "bidirectional"))
    )
    (net (code "33") (name "/SDA") (class "Default")
      (node (ref "IC2") (pin "5") (pinfunction "SDA_5") (pintype "bidirectional"))
      (node (ref "R36") (pin "1") (pinfunction "1_1") (pintype "passive"))
      (node (ref "U1") (pin "55") (pinfunction "SPI3_SCK/I2S3_SCK/PB3_55") (pintype "bidirectional"))
    )
    (net (code "34") (name "/SWCLK") (class "Default")
      (node (ref "JP11") (pin "2") (pinfunction "2_2") (pintype "passive"))
      (node (ref "U1") (pin "49") (pinfunction "PA14/JTCK/SWCLK_49") (pintype "bidirectional"))
    )
    (net (code "35") (name "/SWDIO") (class "Default")
      (node (ref "JP11") (pin "4") (pinfunction "4_4") (pintype "passive"))
      (node (ref "U1") (pin "46") (pinfunction "PA13/JTMS/SWDIO_46") (pintype "bidirectional"))
    )
    (net (code "36") (name "/TEM1") (class "Default")
      (node (ref "JP1") (pin "2") (pinfunction "2_2") (pintype "passive"))
      (node (ref "R19") (pin "1") (pinfunction "1_1") (pintype "passive"))
      (node (ref "U1") (pin "25") (pinfunction "ADC12_IN15/PC5_25") (pintype "bidirectional"))
    )
    (net (code "37") (name "/TEM2") (class "Default")
      (node (ref "JP4") (pin "2") (pinfunction "2_2") (pintype "passive"))
      (node (ref "R31") (pin "1") (pinfunction "1_1") (pintype "passive"))
      (node (ref "U1") (pin "26") (pinfunction "ADC12_IN8/PB0_26") (pintype "bidirectional"))
    )
    (net (code "38") (name "/TPLCLK") (class "Default")
      (node (ref "IC*1") (pin "4") (pinfunction "SCLK_4") (pintype "passive"))
      (node (ref "U1") (pin "61") (pinfunction "TIM4_CH3/SDIO_D4/PB8_61") (pintype "bidirectional"))
    )
    (net (code "39") (name "/TPLCS") (class "Default")
      (node (ref "IC*1") (pin "6") (pinfunction "CS_6") (pintype "passive"))
      (node (ref "U1") (pin "2") (pinfunction "RTC/TAMPER/PC13_2") (pintype "bidirectional"))
    )
    (net (code "40") (name "/TPLDLN") (class "Default")
      (node (ref "IC*1") (pin "5") (pinfunction "DLN_5") (pintype "passive"))
      (node (ref "U1") (pin "56") (pinfunction "SPI3_MISO/NJTRST/PB4_56") (pintype "bidirectional"))
    )
    (net (code "41") (name "/TX1") (class "Default")
      (node (ref "JP7") (pin "2") (pinfunction "2_2") (pintype "passive"))
      (node (ref "U1") (pin "42") (pinfunction "PA9/USART1_TX_42") (pintype "bidirectional"))
    )
    (net (code "42") (name "/TX2") (class "Default")
      (node (ref "IC1") (pin "10") (pinfunction "DIN2_10") (pintype "passive"))
      (node (ref "U1") (pin "16") (pinfunction "USART2_TX/PA2_16") (pintype "bidirectional"))
    )
    (net (code "43") (name "/TX3") (class "Default")
      (node (ref "JP13") (pin "11") (pinfunction "11_11") (pintype "passive"))
      (node (ref "JP14") (pin "2") (pinfunction "2_2") (pintype "passive"))
      (node (ref "U1") (pin "29") (pinfunction "I2C2_SCL/USART3_TX/PB10_29") (pintype "bidirectional"))
    )
    (net (code "44") (name "/WS2812") (class "Default")
      (node (ref "JP10") (pin "2") (pinfunction "2_2") (pintype "passive"))
      (node (ref "U1") (pin "37") (pinfunction "SDIO_D6/I2S2_MCK/PC6_37") (pintype "bidirectional"))
    )
    (net (code "45") (name "3.3V") (class "Default")
      (node (ref "C20") (pin "2") (pinfunction "2_2") (pintype "passive"))
      (node (ref "C22") (pin "2") (pinfunction "2_2") (pintype "passive"))
      (node (ref "C26") (pin "1") (pinfunction "1_1") (pintype "passive"))
      (node (ref "C31") (pin "2") (pinfunction "2_2") (pintype "passive"))
      (node (ref "C33") (pin "2") (pinfunction "2_2") (pintype "passive"))
      (node (ref "C34") (pin "2") (pinfunction "2_2") (pintype "passive"))
      (node (ref "C39") (pin "2") (pinfunction "2_2") (pintype "passive"))
      (node (ref "E3") (pin "1") (pinfunction "A_1") (pintype "passive"))
      (node (ref "IC*1") (pin "2") (pinfunction "VDD_2") (pintype "passive"))
      (node (ref "IC1") (pin "16") (pinfunction "VCC_16") (pintype "passive"))
      (node (ref "IC2") (pin "8") (pinfunction "VCC_8") (pintype "power_in"))
      (node (ref "JP1") (pin "1") (pinfunction "1_1") (pintype "passive"))
      (node (ref "JP11") (pin "8") (pinfunction "8_8") (pintype "passive"))
      (node (ref "JP2") (pin "1") (pinfunction "1_1") (pintype "passive"))
      (node (ref "JP4") (pin "1") (pinfunction "1_1") (pintype "passive"))
      (node (ref "JP6") (pin "1") (pinfunction "1_1") (pintype "passive"))
      (node (ref "JP7") (pin "4") (pinfunction "4_4") (pintype "passive"))
      (node (ref "LED5") (pin "1") (pinfunction "A_1") (pintype "passive"))
      (node (ref "LED6") (pin "1") (pinfunction "A_1") (pintype "passive"))
      (node (ref "LED7") (pin "1") (pinfunction "A_1") (pintype "passive"))
      (node (ref "R12") (pin "1") (pinfunction "1_1") (pintype "passive"))
      (node (ref "R14") (pin "1") (pinfunction "1_1") (pintype "passive"))
      (node (ref "R15") (pin "2") (pinfunction "2_2") (pintype "passive"))
      (node (ref "R16") (pin "2") (pinfunction "2_2") (pintype "passive"))
      (node (ref "R17") (pin "1") (pinfunction "1_1") (pintype "passive"))
      (node (ref "R19") (pin "2") (pinfunction "2_2") (pintype "passive"))
      (node (ref "R2") (pin "2") (pinfunction "2_2") (pintype "passive"))
      (node (ref "R22") (pin "2") (pinfunction "2_2") (pintype "passive"))
      (node (ref "R25") (pin "2") (pinfunction "2_2") (pintype "passive"))
      (node (ref "R26") (pin "2") (pinfunction "2_2") (pintype "passive"))
      (node (ref "R3") (pin "2") (pinfunction "2_2") (pintype "passive"))
      (node (ref "R31") (pin "2") (pinfunction "2_2") (pintype "passive"))
      (node (ref "R32") (pin "2") (pinfunction "2_2") (pintype "passive"))
      (node (ref "R33") (pin "2") (pinfunction "2_2") (pintype "passive"))
      (node (ref "R36") (pin "2") (pinfunction "2_2") (pintype "passive"))
      (node (ref "R7") (pin "2") (pinfunction "2_2") (pintype "passive"))
      (node (ref "R8") (pin "2") (pinfunction "2_2") (pintype "passive"))
      (node (ref "S1") (pin "3") (pinfunction "3_3") (pintype "passive"))
      (node (ref "V1") (pin "2") (pinfunction "Vout_2") (pintype "passive"))
    )
    (net (code "46") (name "3.3VM") (class "Default")
      (node (ref "C15") (pin "2") (pinfunction "2_2") (pintype "passive"))
      (node (ref "C16") (pin "2") (pinfunction "2_2") (pintype "passive"))
      (node (ref "C17") (pin "2") (pinfunction "2_2") (pintype "passive"))
      (node (ref "C18") (pin "2") (pinfunction "2_2") (pintype "passive"))
      (node (ref "R14") (pin "2") (pinfunction "2_2") (pintype "passive"))
      (node (ref "R17") (pin "2") (pinfunction "2_2") (pintype "passive"))
      (node (ref "R21") (pin "2") (pinfunction "2_2") (pintype "passive"))
      (node (ref "U1") (pin "19") (pinfunction "VDD_4_19") (pintype "power_in"))
      (node (ref "U1") (pin "32") (pinfunction "VDD_1_32") (pintype "power_in"))
      (node (ref "U1") (pin "48") (pinfunction "VDD_2_48") (pintype "power_in"))
      (node (ref "U1") (pin "64") (pinfunction "VDD_3_64") (pintype "power_in"))
    )
    (net (code "47") (name "5V") (class "Default")
      (node (ref "C40") (pin "1") (pinfunction "1_1") (pintype "passive"))
      (node (ref "E2") (pin "1") (pinfunction "A_1") (pintype "passive"))
      (node (ref "E5") (pin "1") (pinfunction "A_1") (pintype "passive"))
      (node (ref "JP10") (pin "1") (pinfunction "1_1") (pintype "passive"))
      (node (ref "JP11") (pin "10") (pinfunction "10_10") (pintype "passive"))
      (node (ref "JP3") (pin "1") (pinfunction "1_1") (pintype "passive"))
      (node (ref "L2") (pin "1") (pinfunction "1_1") (pintype "passive"))
      (node (ref "LED8") (pin "1") (pinfunction "A_1") (pintype "passive"))
      (node (ref "LED9") (pin "1") (pinfunction "A_1") (pintype "passive"))
      (node (ref "M5") (pin "3") (pinfunction "+Vout_3") (pintype "passive"))
    )
    (net (code "48") (name "5VUSB") (class "Default")
      (node (ref "JP12") (pin "6") (pinfunction "6_6") (pintype "passive"))
      (node (ref "USB1") (pin "1") (pinfunction "+5V_1") (pintype "passive"))
    )
    (net (code "49") (name "12V") (class "Default")
      (node (ref "C41") (pin "1") (pinfunction "1_1") (pintype "passive"))
      (node (ref "C42") (pin "1") (pinfunction "1_1") (pintype "passive"))
      (node (ref "E4") (pin "1") (pinfunction "A_1") (pintype "passive"))
      (node (ref "E6") (pin "1") (pinfunction "A_1") (pintype "passive"))
      (node (ref "J2") (pin "4") (pinfunction "C_4") (pintype "passive"))
      (node (ref "J3") (pin "4") (pinfunction "C_4") (pintype "passive"))
      (node (ref "J5") (pin "4") (pinfunction "C_4") (pintype "passive"))
      (node (ref "J6") (pin "4") (pinfunction "C_4") (pintype "passive"))
      (node (ref "JK1") (pin "2") (pinfunction "2_2") (pintype "passive"))
      (node (ref "JK2") (pin "2") (pinfunction "2_2") (pintype "passive"))
      (node (ref "JK3") (pin "2") (pinfunction "2_2") (pintype "passive"))
      (node (ref "JK4") (pin "2") (pinfunction "2_2") (pintype "passive"))
      (node (ref "JP8") (pin "10") (pinfunction "10_10") (pintype "passive"))
      (node (ref "L3") (pin "1") (pinfunction "1_1") (pintype "passive"))
      (node (ref "L4") (pin "1") (pinfunction "1_1") (pintype "passive"))
      (node (ref "VD1") (pin "2") (pinfunction "K_2") (pintype "passive"))
      (node (ref "VD2") (pin "2") (pinfunction "K_2") (pintype "passive"))
      (node (ref "VD3") (pin "2") (pinfunction "K_2") (pintype "passive"))
      (node (ref "VD4") (pin "2") (pinfunction "K_2") (pintype "passive"))
      (node (ref "ZR1") (pin "1") (pinfunction "1_1") (pintype "passive"))
    )
    (net (code "50") (name "GND") (class "Default")
      (node (ref "C12") (pin "1") (pinfunction "1_1") (pintype "passive"))
      (node (ref "C13") (pin "1") (pinfunction "1_1") (pintype "passive"))
      (node (ref "C14") (pin "2") (pinfunction "2_2") (pintype "passive"))
      (node (ref "C15") (pin "1") (pinfunction "1_1") (pintype "passive"))
      (node (ref "C16") (pin "1") (pinfunction "1_1") (pintype "passive"))
      (node (ref "C17") (pin "1") (pinfunction "1_1") (pintype "passive"))
      (node (ref "C18") (pin "1") (pinfunction "1_1") (pintype "passive"))
      (node (ref "C19") (pin "2") (pinfunction "2_2") (pintype "passive"))
      (node (ref "C20") (pin "1") (pinfunction "1_1") (pintype "passive"))
      (node (ref "C21") (pin "2") (pinfunction "2_2") (pintype "passive"))
      (node (ref "C22") (pin "1") (pinfunction "1_1") (pintype "passive"))
      (node (ref "C23") (pin "2") (pinfunction "2_2") (pintype "passive"))
      (node (ref "C24") (pin "2") (pinfunction "2_2") (pintype "passive"))
      (node (ref "C25") (pin "1") (pinfunction "1_1") (pintype "passive"))
      (node (ref "C26") (pin "2") (pinfunction "2_2") (pintype "passive"))
      (node (ref "C28") (pin "1") (pinfunction "1_1") (pintype "passive"))
      (node (ref "C30") (pin "1") (pinfunction "1_1") (pintype "passive"))
      (node (ref "C31") (pin "1") (pinfunction "1_1") (pintype "passive"))
      (node (ref "C33") (pin "1") (pinfunction "1_1") (pintype "passive"))
      (node (ref "C34") (pin "1") (pinfunction "1_1") (pintype "passive"))
      (node (ref "C38") (pin "1") (pinfunction "1_1") (pintype "passive"))
      (node (ref "C39") (pin "1") (pinfunction "1_1") (pintype "passive"))
      (node (ref "C41") (pin "2") (pinfunction "2_2") (pintype "passive"))
      (node (ref "C42") (pin "2") (pinfunction "2_2") (pintype "passive"))
      (node (ref "C43") (pin "1") (pinfunction "1_1") (pintype "passive"))
      (node (ref "E2") (pin "2") (pinfunction "K_2") (pintype "passive"))
      (node (ref "E3") (pin "2") (pinfunction "K_2") (pintype "passive"))
      (node (ref "E4") (pin "2") (pinfunction "K_2") (pintype "passive"))
      (node (ref "E5") (pin "2") (pinfunction "K_2") (pintype "passive"))
      (node (ref "E6") (pin "2") (pinfunction "K_2") (pintype "passive"))
      (node (ref "IC*1") (pin "3") (pinfunction "GND_3") (pintype "passive"))
      (node (ref "IC1") (pin "15") (pinfunction "GND_15") (pintype "passive"))
      (node (ref "IC2") (pin "1") (pinfunction "A0_1") (pintype "input"))
      (node (ref "IC2") (pin "2") (pinfunction "A1_2") (pintype "input"))
      (node (ref "IC2") (pin "3") (pinfunction "A2_3") (pintype "input"))
      (node (ref "IC2") (pin "4") (pinfunction "GND_4") (pintype "passive"))
      (node (ref "IC2") (pin "7") (pinfunction "WP_7") (pintype "passive"))
      (node (ref "JP1") (pin "3") (pinfunction "3_3") (pintype "passive"))
      (node (ref "JP10") (pin "3") (pinfunction "3_3") (pintype "passive"))
      (node (ref "JP11") (pin "6") (pinfunction "6_6") (pintype "passive"))
      (node (ref "JP12") (pin "3") (pinfunction "3_3") (pintype "passive"))
      (node (ref "JP13") (pin "2") (pinfunction "2_2") (pintype "passive"))
      (node (ref "JP13") (pin "3") (pinfunction "3_3") (pintype "passive"))
      (node (ref "JP14") (pin "3") (pinfunction "3_3") (pintype "passive"))
      (node (ref "JP2") (pin "3") (pinfunction "3_3") (pintype "passive"))
      (node (ref "JP3") (pin "3") (pinfunction "3_3") (pintype "passive"))
      (node (ref "JP4") (pin "3") (pinfunction "3_3") (pintype "passive"))
      (node (ref "JP5") (pin "1") (pinfunction "1_1") (pintype "passive"))
      (node (ref "JP6") (pin "3") (pinfunction "3_3") (pintype "passive"))
      (node (ref "JP7") (pin "1") (pinfunction "1_1") (pintype "passive"))
      (node (ref "JP8") (pin "9") (pinfunction "9_9") (pintype "passive"))
      (node (ref "M5") (pin "1") (pinfunction "-Vin_1") (pintype "passive"))
      (node (ref "M5") (pin "4") (pinfunction "GND_4") (pintype "passive"))
      (node (ref "Q1") (pin "2") (pinfunction "E_2") (pintype "passive"))
      (node (ref "Q2") (pin "2") (pinfunction "E_2") (pintype "passive"))
      (node (ref "Q3") (pin "2") (pinfunction "E_2") (pintype "passive"))
      (node (ref "Q4") (pin "2") (pinfunction "E_2") (pintype "passive"))
      (node (ref "Q5") (pin "2") (pinfunction "E_2") (pintype "passive"))
      (node (ref "Q6") (pin "2") (pinfunction "E_2") (pintype "passive"))
      (node (ref "R11") (pin "1") (pinfunction "1_1") (pintype "passive"))
      (node (ref "R20") (pin "1") (pinfunction "1_1") (pintype "passive"))
      (node (ref "R23") (pin "1") (pinfunction "1_1") (pintype "passive"))
      (node (ref "R29") (pin "1") (pinfunction "1_1") (pintype "passive"))
      (node (ref "R34") (pin "1") (pinfunction "1_1") (pintype "passive"))
      (node (ref "R35") (pin "1") (pinfunction "1_1") (pintype "passive"))
      (node (ref "R41") (pin "1") (pinfunction "1_1") (pintype "passive"))
      (node (ref "R48") (pin "1") (pinfunction "1_1") (pintype "passive"))
      (node (ref "R5") (pin "1") (pinfunction "1_1") (pintype "passive"))
      (node (ref "R9") (pin "2") (pinfunction "2_2") (pintype "passive"))
      (node (ref "S1") (pin "1") (pinfunction "1_1") (pintype "passive"))
      (node (ref "SW1") (pin "2") (pinfunction "2_2") (pintype "passive"))
      (node (ref "U1") (pin "12") (pinfunction "VSSA_12") (pintype "power_in"))
      (node (ref "U1") (pin "18") (pinfunction "VSS_4_18") (pintype "power_in"))
      (node (ref "U1") (pin "31") (pinfunction "VSS_1_31") (pintype "passive"))
      (node (ref "U1") (pin "47") (pinfunction "VSS_2_47") (pintype "passive"))
      (node (ref "U1") (pin "63") (pinfunction "VSS_3_63") (pintype "power_in"))
      (node (ref "USB1") (pin "4") (pinfunction "ID_4") (pintype "passive"))
      (node (ref "USB1") (pin "5") (pinfunction "GND_5") (pintype "passive"))
      (node (ref "V1") (pin "1") (pinfunction "GND_1") (pintype "passive"))
      (node (ref "ZR1") (pin "2") (pinfunction "2_2") (pintype "passive"))
    )
    (net (code "51") (name "Net-(C25-Pad2)") (class "Default")
      (node (ref "C25") (pin "2") (pinfunction "2_2") (pintype "passive"))
      (node (ref "JP3") (pin "2") (pinfunction "2_2") (pintype "passive"))
      (node (ref "R24") (pin "2") (pinfunction "2_2") (pintype "passive"))
    )
    (net (code "52") (name "Net-(IC*1-H)") (class "Default")
      (node (ref "IC*1") (pin "8") (pinfunction "H_8") (pintype "passive"))
      (node (ref "JP9") (pin "2") (pinfunction "2_2") (pintype "passive"))
      (node (ref "R47") (pin "1") (pinfunction "1_1") (pintype "passive"))
    )
    (net (code "53") (name "Net-(IC*1-W)") (class "Default")
      (node (ref "IC*1") (pin "1") (pinfunction "W_1") (pintype "passive"))
      (node (ref "JP9") (pin "3") (pinfunction "3_3") (pintype "passive"))
    )
    (net (code "54") (name "Net-(IC1-C1+)") (class "Default")
      (node (ref "C27") (pin "2") (pinfunction "2_2") (pintype "passive"))
      (node (ref "IC1") (pin "1") (pinfunction "C1+_1") (pintype "passive"))
    )
    (net (code "55") (name "Net-(IC1-C1-)") (class "Default")
      (node (ref "C27") (pin "1") (pinfunction "1_1") (pintype "passive"))
      (node (ref "IC1") (pin "3") (pinfunction "C1-_3") (pintype "passive"))
    )
    (net (code "56") (name "Net-(IC1-C2+)") (class "Default")
      (node (ref "C29") (pin "2") (pinfunction "2_2") (pintype "passive"))
      (node (ref "IC1") (pin "4") (pinfunction "C2+_4") (pintype "passive"))
    )
    (net (code "57") (name "Net-(IC1-C2-)") (class "Default")
      (node (ref "C29") (pin "1") (pinfunction "1_1") (pintype "passive"))
      (node (ref "IC1") (pin "5") (pinfunction "C2-_5") (pintype "passive"))
    )
    (net (code "58") (name "Net-(IC1-DOUT2)") (class "Default")
      (node (ref "IC1") (pin "7") (pinfunction "DOUT2_7") (pintype "passive"))
      (node (ref "JP5") (pin "3") (pinfunction "3_3") (pintype "passive"))
    )
    (net (code "59") (name "Net-(IC1-RIN2)") (class "Default")
      (node (ref "IC1") (pin "8") (pinfunction "RIN2_8") (pintype "passive"))
      (node (ref "JP5") (pin "2") (pinfunction "2_2") (pintype "passive"))
    )
    (net (code "60") (name "Net-(IC1-V+)") (class "Default")
      (node (ref "C28") (pin "2") (pinfunction "2_2") (pintype "passive"))
      (node (ref "IC1") (pin "2") (pinfunction "V+_2") (pintype "passive"))
    )
    (net (code "61") (name "Net-(IC1-V-)") (class "Default")
      (node (ref "C30") (pin "2") (pinfunction "2_2") (pintype "passive"))
      (node (ref "IC1") (pin "6") (pinfunction "V-_6") (pintype "passive"))
    )
    (net (code "62") (name "Net-(J2-A)") (class "Default")
      (node (ref "J2") (pin "1") (pinfunction "A_1") (pintype "passive"))
      (node (ref "R3") (pin "1") (pinfunction "1_1") (pintype "passive"))
    )
    (net (code "63") (name "Net-(J2-E)") (class "Default")
      (node (ref "J2") (pin "3") (pinfunction "E_3") (pintype "passive"))
      (node (ref "R4") (pin "1") (pinfunction "1_1") (pintype "passive"))
    )
    (net (code "64") (name "Net-(J3-A)") (class "Default")
      (node (ref "J3") (pin "1") (pinfunction "A_1") (pintype "passive"))
      (node (ref "R8") (pin "1") (pinfunction "1_1") (pintype "passive"))
    )
    (net (code "65") (name "Net-(J3-E)") (class "Default")
      (node (ref "J3") (pin "3") (pinfunction "E_3") (pintype "passive"))
      (node (ref "R10") (pin "1") (pinfunction "1_1") (pintype "passive"))
    )
    (net (code "66") (name "Net-(J5-A)") (class "Default")
      (node (ref "J5") (pin "1") (pinfunction "A_1") (pintype "passive"))
      (node (ref "R16") (pin "1") (pinfunction "1_1") (pintype "passive"))
    )
    (net (code "67") (name "Net-(J5-E)") (class "Default")
      (node (ref "J5") (pin "3") (pinfunction "E_3") (pintype "passive"))
      (node (ref "R18") (pin "1") (pinfunction "1_1") (pintype "passive"))
    )
    (net (code "68") (name "Net-(J6-A)") (class "Default")
      (node (ref "J6") (pin "1") (pinfunction "A_1") (pintype "passive"))
      (node (ref "R26") (pin "1") (pinfunction "1_1") (pintype "passive"))
    )
    (net (code "69") (name "Net-(J6-E)") (class "Default")
      (node (ref "J6") (pin "3") (pinfunction "E_3") (pintype "passive"))
      (node (ref "R27") (pin "1") (pinfunction "1_1") (pintype "passive"))
    )
    (net (code "70") (name "Net-(JP9-Pad1)") (class "Default")
      (node (ref "JP9") (pin "1") (pinfunction "1_1") (pintype "passive"))
      (node (ref "R47") (pin "2") (pinfunction "2_2") (pintype "passive"))
    )
    (net (code "71") (name "Net-(JP13-Pad1)") (class "Default")
      (node (ref "JP13") (pin "1") (pinfunction "1_1") (pintype "passive"))
      (node (ref "L4") (pin "2") (pinfunction "2_2") (pintype "passive"))
    )
    (net (code "72") (name "Net-(LED1-A)") (class "Default")
      (node (ref "LED1") (pin "1") (pinfunction "A_1") (pintype "passive"))
      (node (ref "R2") (pin "1") (pinfunction "1_1") (pintype "passive"))
    )
    (net (code "73") (name "Net-(LED2-A)") (class "Default")
      (node (ref "LED2") (pin "1") (pinfunction "A_1") (pintype "passive"))
      (node (ref "R7") (pin "1") (pinfunction "1_1") (pintype "passive"))
    )
    (net (code "74") (name "Net-(LED3-A)") (class "Default")
      (node (ref "LED3") (pin "1") (pinfunction "A_1") (pintype "passive"))
      (node (ref "R15") (pin "1") (pinfunction "1_1") (pintype "passive"))
    )
    (net (code "75") (name "Net-(LED4-A)") (class "Default")
      (node (ref "LED4") (pin "1") (pinfunction "A_1") (pintype "passive"))
      (node (ref "R25") (pin "1") (pinfunction "1_1") (pintype "passive"))
    )
    (net (code "76") (name "Net-(LED5-K)") (class "Default")
      (node (ref "LED5") (pin "2") (pinfunction "K_2") (pintype "passive"))
      (node (ref "R41") (pin "2") (pinfunction "2_2") (pintype "passive"))
    )
    (net (code "77") (name "Net-(LED6-K)") (class "Default")
      (node (ref "LED6") (pin "2") (pinfunction "K_2") (pintype "passive"))
      (node (ref "R42") (pin "2") (pinfunction "2_2") (pintype "passive"))
    )
    (net (code "78") (name "Net-(LED7-K)") (class "Default")
      (node (ref "LED7") (pin "2") (pinfunction "K_2") (pintype "passive"))
      (node (ref "R43") (pin "2") (pinfunction "2_2") (pintype "passive"))
    )
    (net (code "79") (name "Net-(LED8-K)") (class "Default")
      (node (ref "LED8") (pin "2") (pinfunction "K_2") (pintype "passive"))
      (node (ref "R1") (pin "2") (pinfunction "2_2") (pintype "passive"))
    )
    (net (code "80") (name "Net-(LED9-K)") (class "Default")
      (node (ref "LED9") (pin "2") (pinfunction "K_2") (pintype "passive"))
      (node (ref "R6") (pin "2") (pinfunction "2_2") (pintype "passive"))
    )
    (net (code "81") (name "Net-(M5-+Vin)") (class "Default")
      (node (ref "L3") (pin "2") (pinfunction "2_2") (pintype "passive"))
      (node (ref "M5") (pin "2") (pinfunction "+Vin_2") (pintype "passive"))
    )
    (net (code "82") (name "Net-(Q1-B)") (class "Default")
      (node (ref "Q1") (pin "1") (pinfunction "B_1") (pintype "passive"))
      (node (ref "R4") (pin "2") (pinfunction "2_2") (pintype "passive"))
      (node (ref "R5") (pin "2") (pinfunction "2_2") (pintype "passive"))
    )
    (net (code "83") (name "Net-(Q1-C)") (class "Default")
      (node (ref "JK1") (pin "1") (pinfunction "1_1") (pintype "passive"))
      (node (ref "Q1") (pin "3") (pinfunction "C_3") (pintype "passive"))
      (node (ref "VD1") (pin "1") (pinfunction "A_1") (pintype "passive"))
    )
    (net (code "84") (name "Net-(Q2-B)") (class "Default")
      (node (ref "Q2") (pin "1") (pinfunction "B_1") (pintype "passive"))
      (node (ref "R10") (pin "2") (pinfunction "2_2") (pintype "passive"))
      (node (ref "R11") (pin "2") (pinfunction "2_2") (pintype "passive"))
    )
    (net (code "85") (name "Net-(Q2-C)") (class "Default")
      (node (ref "JK2") (pin "1") (pinfunction "1_1") (pintype "passive"))
      (node (ref "Q2") (pin "3") (pinfunction "C_3") (pintype "passive"))
      (node (ref "VD2") (pin "1") (pinfunction "A_1") (pintype "passive"))
    )
    (net (code "86") (name "Net-(Q3-B)") (class "Default")
      (node (ref "Q3") (pin "1") (pinfunction "B_1") (pintype "passive"))
      (node (ref "R18") (pin "2") (pinfunction "2_2") (pintype "passive"))
      (node (ref "R20") (pin "2") (pinfunction "2_2") (pintype "passive"))
    )
    (net (code "87") (name "Net-(Q3-C)") (class "Default")
      (node (ref "JK3") (pin "1") (pinfunction "1_1") (pintype "passive"))
      (node (ref "Q3") (pin "3") (pinfunction "C_3") (pintype "passive"))
      (node (ref "VD3") (pin "1") (pinfunction "A_1") (pintype "passive"))
    )
    (net (code "88") (name "Net-(Q4-B)") (class "Default")
      (node (ref "Q4") (pin "1") (pinfunction "B_1") (pintype "passive"))
      (node (ref "R27") (pin "2") (pinfunction "2_2") (pintype "passive"))
      (node (ref "R29") (pin "2") (pinfunction "2_2") (pintype "passive"))
    )
    (net (code "89") (name "Net-(Q4-C)") (class "Default")
      (node (ref "JK4") (pin "1") (pinfunction "1_1") (pintype "passive"))
      (node (ref "Q4") (pin "3") (pinfunction "C_3") (pintype "passive"))
      (node (ref "VD4") (pin "1") (pinfunction "A_1") (pintype "passive"))
    )
    (net (code "90") (name "Net-(Q5-B)") (class "Default")
      (node (ref "Q5") (pin "1") (pinfunction "B_1") (pintype "passive"))
      (node (ref "R28") (pin "1") (pinfunction "1_1") (pintype "passive"))
      (node (ref "R34") (pin "2") (pinfunction "2_2") (pintype "passive"))
    )
    (net (code "91") (name "Net-(Q5-C)") (class "Default")
      (node (ref "Q5") (pin "3") (pinfunction "C_3") (pintype "passive"))
      (node (ref "R1") (pin "1") (pinfunction "1_1") (pintype "passive"))
    )
    (net (code "92") (name "Net-(Q6-B)") (class "Default")
      (node (ref "Q6") (pin "1") (pinfunction "B_1") (pintype "passive"))
      (node (ref "R30") (pin "1") (pinfunction "1_1") (pintype "passive"))
      (node (ref "R35") (pin "2") (pinfunction "2_2") (pintype "passive"))
    )
    (net (code "93") (name "Net-(Q6-C)") (class "Default")
      (node (ref "Q6") (pin "3") (pinfunction "C_3") (pintype "passive"))
      (node (ref "R6") (pin "1") (pinfunction "1_1") (pintype "passive"))
    )
    (net (code "94") (name "Net-(R40-Pad2)") (class "Default")
      (node (ref "R40") (pin "2") (pinfunction "2_2") (pintype "passive"))
      (node (ref "S1") (pin "2") (pinfunction "2_2") (pintype "passive"))
    )
    (net (code "95") (name "Net-(U1-BOOT1{slash}PB2)") (class "Default")
      (node (ref "R9") (pin "1") (pinfunction "1_1") (pintype "passive"))
      (node (ref "U1") (pin "28") (pinfunction "BOOT1/PB2_28") (pintype "bidirectional"))
    )
    (net (code "96") (name "Net-(U1-VDDA)") (class "Default")
      (node (ref "C12") (pin "2") (pinfunction "2_2") (pintype "passive"))
      (node (ref "C13") (pin "2") (pinfunction "2_2") (pintype "passive"))
      (node (ref "R12") (pin "2") (pinfunction "2_2") (pintype "passive"))
      (node (ref "U1") (pin "13") (pinfunction "VDDA_13") (pintype "power_in"))
    )
    (net (code "97") (name "Net-(V1-Vin)") (class "Default")
      (node (ref "L2") (pin "2") (pinfunction "2_2") (pintype "passive"))
      (node (ref "V1") (pin "3") (pinfunction "Vin_3") (pintype "passive"))
    )
    (net (code "98") (name "unconnected-(C38-Pad2)") (class "Default")
      (node (ref "C38") (pin "2") (pinfunction "2_2") (pintype "passive"))
    )
    (net (code "99") (name "unconnected-(C40-Pad2)") (class "Default")
      (node (ref "C40") (pin "2") (pinfunction "2_2") (pintype "passive"))
    )
    (net (code "100") (name "unconnected-(IC*1-L-Pad7)") (class "Default")
      (node (ref "IC*1") (pin "7") (pinfunction "L_7") (pintype "passive"))
    )
    (net (code "101") (name "unconnected-(IC1-DIN1-Pad11)") (class "Default")
      (node (ref "IC1") (pin "11") (pinfunction "DIN1_11") (pintype "passive"))
    )
    (net (code "102") (name "unconnected-(IC1-DOUT1-Pad14)") (class "Default")
      (node (ref "IC1") (pin "14") (pinfunction "DOUT1_14") (pintype "passive"))
    )
    (net (code "103") (name "unconnected-(IC1-RIN1-Pad13)") (class "Default")
      (node (ref "IC1") (pin "13") (pinfunction "RIN1_13") (pintype "passive"))
    )
    (net (code "104") (name "unconnected-(IC1-ROUT1-Pad12)") (class "Default")
      (node (ref "IC1") (pin "12") (pinfunction "ROUT1_12") (pintype "passive"))
    )
    (net (code "105") (name "unconnected-(JP11-Pad1)") (class "Default")
      (node (ref "JP11") (pin "1") (pinfunction "1_1") (pintype "passive"))
    )
    (net (code "106") (name "unconnected-(JP11-Pad3)") (class "Default")
      (node (ref "JP11") (pin "3") (pinfunction "3_3") (pintype "passive"))
    )
    (net (code "107") (name "unconnected-(JP11-Pad5)") (class "Default")
      (node (ref "JP11") (pin "5") (pinfunction "5_5") (pintype "passive"))
    )
    (net (code "108") (name "unconnected-(JP11-Pad7)") (class "Default")
      (node (ref "JP11") (pin "7") (pinfunction "7_7") (pintype "passive"))
    )
    (net (code "109") (name "unconnected-(JP11-Pad9)") (class "Default")
      (node (ref "JP11") (pin "9") (pinfunction "9_9") (pintype "passive"))
    )
    (net (code "110") (name "unconnected-(JP12-Pad1)") (class "Default")
      (node (ref "JP12") (pin "1") (pinfunction "1_1") (pintype "passive"))
    )
    (net (code "111") (name "unconnected-(JP12-Pad2)") (class "Default")
      (node (ref "JP12") (pin "2") (pinfunction "2_2") (pintype "passive"))
    )
    (net (code "112") (name "unconnected-(JP12-Pad7)") (class "Default")
      (node (ref "JP12") (pin "7") (pinfunction "7_7") (pintype "passive"))
    )
    (net (code "113") (name "unconnected-(JP12-Pad8)") (class "Default")
      (node (ref "JP12") (pin "8") (pinfunction "8_8") (pintype "passive"))
    )
    (net (code "114") (name "unconnected-(JP12-Pad9)") (class "Default")
      (node (ref "JP12") (pin "9") (pinfunction "9_9") (pintype "passive"))
    )
    (net (code "115") (name "unconnected-(JP12-Pad10)") (class "Default")
      (node (ref "JP12") (pin "10") (pinfunction "10_10") (pintype "passive"))
    )
    (net (code "116") (name "unconnected-(JP13-Pad4)") (class "Default")
      (node (ref "JP13") (pin "4") (pinfunction "4_4") (pintype "passive"))
    )
    (net (code "117") (name "unconnected-(JP13-Pad5)") (class "Default")
      (node (ref "JP13") (pin "5") (pinfunction "5_5") (pintype "passive"))
    )
    (net (code "118") (name "unconnected-(JP13-Pad8)") (class "Default")
      (node (ref "JP13") (pin "8") (pinfunction "8_8") (pintype "passive"))
    )
    (net (code "119") (name "unconnected-(JP13-Pad9)") (class "Default")
      (node (ref "JP13") (pin "9") (pinfunction "9_9") (pintype "passive"))
    )
    (net (code "120") (name "unconnected-(JP13-Pad12)") (class "Default")
      (node (ref "JP13") (pin "12") (pinfunction "12_12") (pintype "passive"))
    )
    (net (code "121") (name "unconnected-(U1-ADC12_IN6{slash}SPI1_MISO{slash}PA6-Pad22)") (class "Default")
      (node (ref "U1") (pin "22") (pinfunction "ADC12_IN6/SPI1_MISO/PA6_22") (pintype "bidirectional"))
    )
    (net (code "122") (name "unconnected-(U1-ADC12_IN7{slash}SPI1_MOSI{slash}PA7-Pad23)") (class "Default")
      (node (ref "U1") (pin "23") (pinfunction "ADC12_IN7/SPI1_MOSI/PA7_23") (pintype "bidirectional"))
    )
    (net (code "123") (name "unconnected-(U1-ADC12_IN9{slash}PB1-Pad27)") (class "Default")
      (node (ref "U1") (pin "27") (pinfunction "ADC12_IN9/PB1_27") (pintype "bidirectional"))
    )
    (net (code "124") (name "unconnected-(U1-ADC12_IN14{slash}PC4-Pad24)") (class "Default")
      (node (ref "U1") (pin "24") (pinfunction "ADC12_IN14/PC4_24") (pintype "bidirectional"))
    )
    (net (code "125") (name "unconnected-(U1-CAN_RX{slash}PA11-Pad44)") (class "Default")
      (node (ref "U1") (pin "44") (pinfunction "CAN_RX/PA11_44") (pintype "bidirectional"))
    )
    (net (code "126") (name "unconnected-(U1-CAN_TX_{slash}PA12-Pad45)") (class "Default")
      (node (ref "U1") (pin "45") (pinfunction "CAN_TX_/PA12_45") (pintype "bidirectional"))
    )
    (net (code "127") (name "unconnected-(U1-DAC_OUT1{slash}SPI1_NSS{slash}PA4-Pad20)") (class "Default")
      (node (ref "U1") (pin "20") (pinfunction "DAC_OUT1/SPI1_NSS/PA4_20") (pintype "bidirectional"))
    )
    (net (code "128") (name "unconnected-(U1-I2S2_SD{slash}SPI2_MOSI{slash}PB15-Pad36)") (class "Default")
      (node (ref "U1") (pin "36") (pinfunction "I2S2_SD/SPI2_MOSI/PB15_36") (pintype "bidirectional"))
    )
    (net (code "129") (name "unconnected-(U1-PA0-WKUP-Pad14)") (class "Default")
      (node (ref "U1") (pin "14") (pinfunction "PA0-WKUP_14") (pintype "bidirectional"))
    )
    (net (code "130") (name "unconnected-(U1-PB9{slash}TIM4_CH4{slash}SDIO_D5-Pad62)") (class "Default")
      (node (ref "U1") (pin "62") (pinfunction "PB9/TIM4_CH4/SDIO_D5_62") (pintype "bidirectional"))
    )
    (net (code "131") (name "unconnected-(U1-PB13{slash}SPI2_SCK{slash}I2S2_CK-Pad34)") (class "Default")
      (node (ref "U1") (pin "34") (pinfunction "PB13/SPI2_SCK/I2S2_CK_34") (pintype "bidirectional"))
    )
    (net (code "132") (name "unconnected-(U1-PC2{slash}ADC123_IN12-Pad10)") (class "Default")
      (node (ref "U1") (pin "10") (pinfunction "PC2/ADC123_IN12_10") (pintype "bidirectional"))
    )
    (net (code "133") (name "unconnected-(U1-PC3{slash}ADC123_IN13-Pad11)") (class "Default")
      (node (ref "U1") (pin "11") (pinfunction "PC3/ADC123_IN13_11") (pintype "bidirectional"))
    )
    (net (code "134") (name "unconnected-(U1-PC8{slash}SDIO_D0-Pad39)") (class "Default")
      (node (ref "U1") (pin "39") (pinfunction "PC8/SDIO_D0_39") (pintype "bidirectional"))
    )
    (net (code "135") (name "unconnected-(U1-PC9{slash}SDIO_D1-Pad40)") (class "Default")
      (node (ref "U1") (pin "40") (pinfunction "PC9/SDIO_D1_40") (pintype "bidirectional"))
    )
    (net (code "136") (name "unconnected-(U1-PC10{slash}SDIO_D2{slash}USART4_TX-Pad51)") (class "Default")
      (node (ref "U1") (pin "51") (pinfunction "PC10/SDIO_D2/USART4_TX_51") (pintype "bidirectional"))
    )
    (net (code "137") (name "unconnected-(U1-PC11{slash}SDIO_D3{slash}USART4_RX-Pad52)") (class "Default")
      (node (ref "U1") (pin "52") (pinfunction "PC11/SDIO_D3/USART4_RX_52") (pintype "bidirectional"))
    )
    (net (code "138") (name "unconnected-(U1-PC12{slash}SDIO_CK{slash}USART5_TX-Pad53)") (class "Default")
      (node (ref "U1") (pin "53") (pinfunction "PC12/SDIO_CK/USART5_TX_53") (pintype "bidirectional"))
    )
    (net (code "139") (name "unconnected-(U1-PD2{slash}SDIO_CMD{slash}USART5_RX-Pad54)") (class "Default")
      (node (ref "U1") (pin "54") (pinfunction "PD2/SDIO_CMD/USART5_RX_54") (pintype "bidirectional"))
    )
    (net (code "140") (name "unconnected-(U1-SPI2_NSS{slash}I2S2_WS{slash}PB12-Pad33)") (class "Default")
      (node (ref "U1") (pin "33") (pinfunction "SPI2_NSS/I2S2_WS/PB12_33") (pintype "bidirectional"))
    )
    (net (code "141") (name "unconnected-(U1-USART1_CK{slash}PA8-Pad41)") (class "Default")
      (node (ref "U1") (pin "41") (pinfunction "USART1_CK/PA8_41") (pintype "bidirectional"))
    )
    (net (code "142") (name "unconnected-(U1-VBAT-Pad1)") (class "Default")
      (node (ref "U1") (pin "1") (pinfunction "VBAT_1") (pintype "power_in"))
    )
  )
)
